# TempPres.net
KiCad netlist of a schematic drawn in Altium Designer
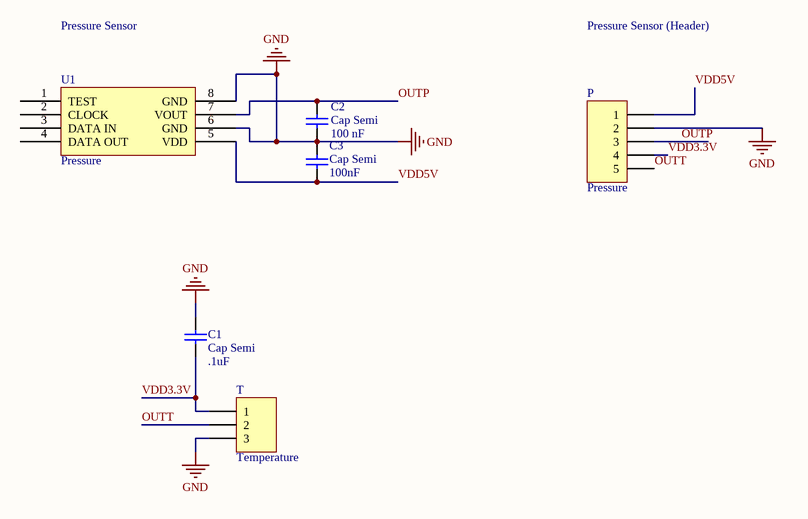
[diagram p0: TempPres.SchDoc]

(export (version "E")
  (design (tool "Eeschema 10.0.6"))
  (components
    (comp (ref "C1")
      (value "Cap Semi")
      (footprint "C1206")
      (description "Capacitor (Semiconductor SIM Model)")
      (fields (field (name "ALTIUM_VALUE") ".1uF") (field (name "PUBLISHER") "Altium Limited"))
      (libsource (lib "Miscellaneous Devices") (part "Cap Semi"))
    )
    (comp (ref "C2")
      (value "Cap Semi")
      (footprint "C1206")
      (description "Capacitor (Semiconductor SIM Model)")
      (fields (field (name "ALTIUM_VALUE") "100 nF") (field (name "PUBLISHER") "Altium Limited"))
      (libsource (lib "Miscellaneous Devices") (part "Cap Semi"))
    )
    (comp (ref "C3")
      (value "Cap Semi")
      (footprint "C1206")
      (description "Capacitor (Semiconductor SIM Model)")
      (fields (field (name "ALTIUM_VALUE") "100nF") (field (name "PUBLISHER") "Altium Limited"))
      (libsource (lib "Miscellaneous Devices") (part "Cap Semi"))
    )
    (comp (ref "P")
      (value "Pressure")
      (footprint "HDR1X5")
      (description "Header, 5-Pin, Right Angle")
      (fields (field (name "PUBLISHER") "Altium Limited"))
      (libsource (lib "Miscellaneous Connectors") (part "Header 5H"))
    )
    (comp (ref "T")
      (value "Temperature")
      (footprint "HDR1X3")
      (description "Header, 3-Pin")
      (fields (field (name "PUBLISHER") "Altium Limited"))
      (libsource (lib "Miscellaneous Connectors") (part "Header 3"))
    )
    (comp (ref "U1") (value "Pressure") (footprint "KP-234") (libsource (lib "KP234") (part "Component_1")))
  )
  (nets
    (net (code "1") (name "/OUTP") (class "Default")
      (node (ref "C2") (pin "2") (pinfunction "2_2") (pintype "passive"))
      (node (ref "P") (pin "3") (pinfunction "3_3") (pintype "passive"))
      (node (ref "U1") (pin "7") (pinfunction "VOUT_7") (pintype "passive"))
    )
    (net (code "2") (name "/OUTT") (class "Default")
      (node (ref "P") (pin "5") (pinfunction "5_5") (pintype "passive"))
      (node (ref "T") (pin "2") (pinfunction "2_2") (pintype "passive"))
    )
    (net (code "3") (name "/VDD3.3V") (class "Default")
      (node (ref "C1") (pin "1") (pinfunction "1_1") (pintype "passive"))
      (node (ref "P") (pin "4") (pinfunction "4_4") (pintype "passive"))
      (node (ref "T") (pin "1") (pinfunction "1_1") (pintype "passive"))
    )
    (net (code "4") (name "/VDD5V") (class "Default")
      (node (ref "C3") (pin "1") (pinfunction "1_1") (pintype "passive"))
      (node (ref "P") (pin "1") (pinfunction "1_1") (pintype "passive"))
      (node (ref "U1") (pin "5") (pinfunction "VDD_5") (pintype "passive"))
    )
    (net (code "5") (name "GND") (class "Default")
      (node (ref "C1") (pin "2") (pinfunction "2_2") (pintype "passive"))
      (node (ref "C2") (pin "1") (pinfunction "1_1") (pintype "passive"))
      (node (ref "C3") (pin "2") (pinfunction "2_2") (pintype "passive"))
      (node (ref "P") (pin "2") (pinfunction "2_2") (pintype "passive"))
      (node (ref "T") (pin "3") (pinfunction "3_3") (pintype "passive"))
      (node (ref "U1") (pin "6") (pinfunction "GND_6") (pintype "passive"))
      (node (ref "U1") (pin "8") (pinfunction "GND_8") (pintype "passive"))
    )
    (net (code "6") (name "unconnected-(U1-CLOCK-Pad2)") (class "Default")
      (node (ref "U1") (pin "2") (pinfunction "CLOCK_2") (pintype "passive"))
    )
    (net (code "7") (name "unconnected-(U1-DATA_IN-Pad3)") (class "Default")
      (node (ref "U1") (pin "3") (pinfunction "DATA_IN_3") (pintype "passive"))
    )
    (net (code "8") (name "unconnected-(U1-DATA_OUT-Pad4)") (class "Default")
      (node (ref "U1") (pin "4") (pinfunction "DATA_OUT_4") (pintype "passive"))
    )
    (net (code "9") (name "unconnected-(U1-TEST-Pad1)") (class "Default")
      (node (ref "U1") (pin "1") (pinfunction "TEST_1") (pintype "passive"))
    )
  )
)
